# ESC_V1.net
KiCad netlist of a schematic drawn in Altium Designer
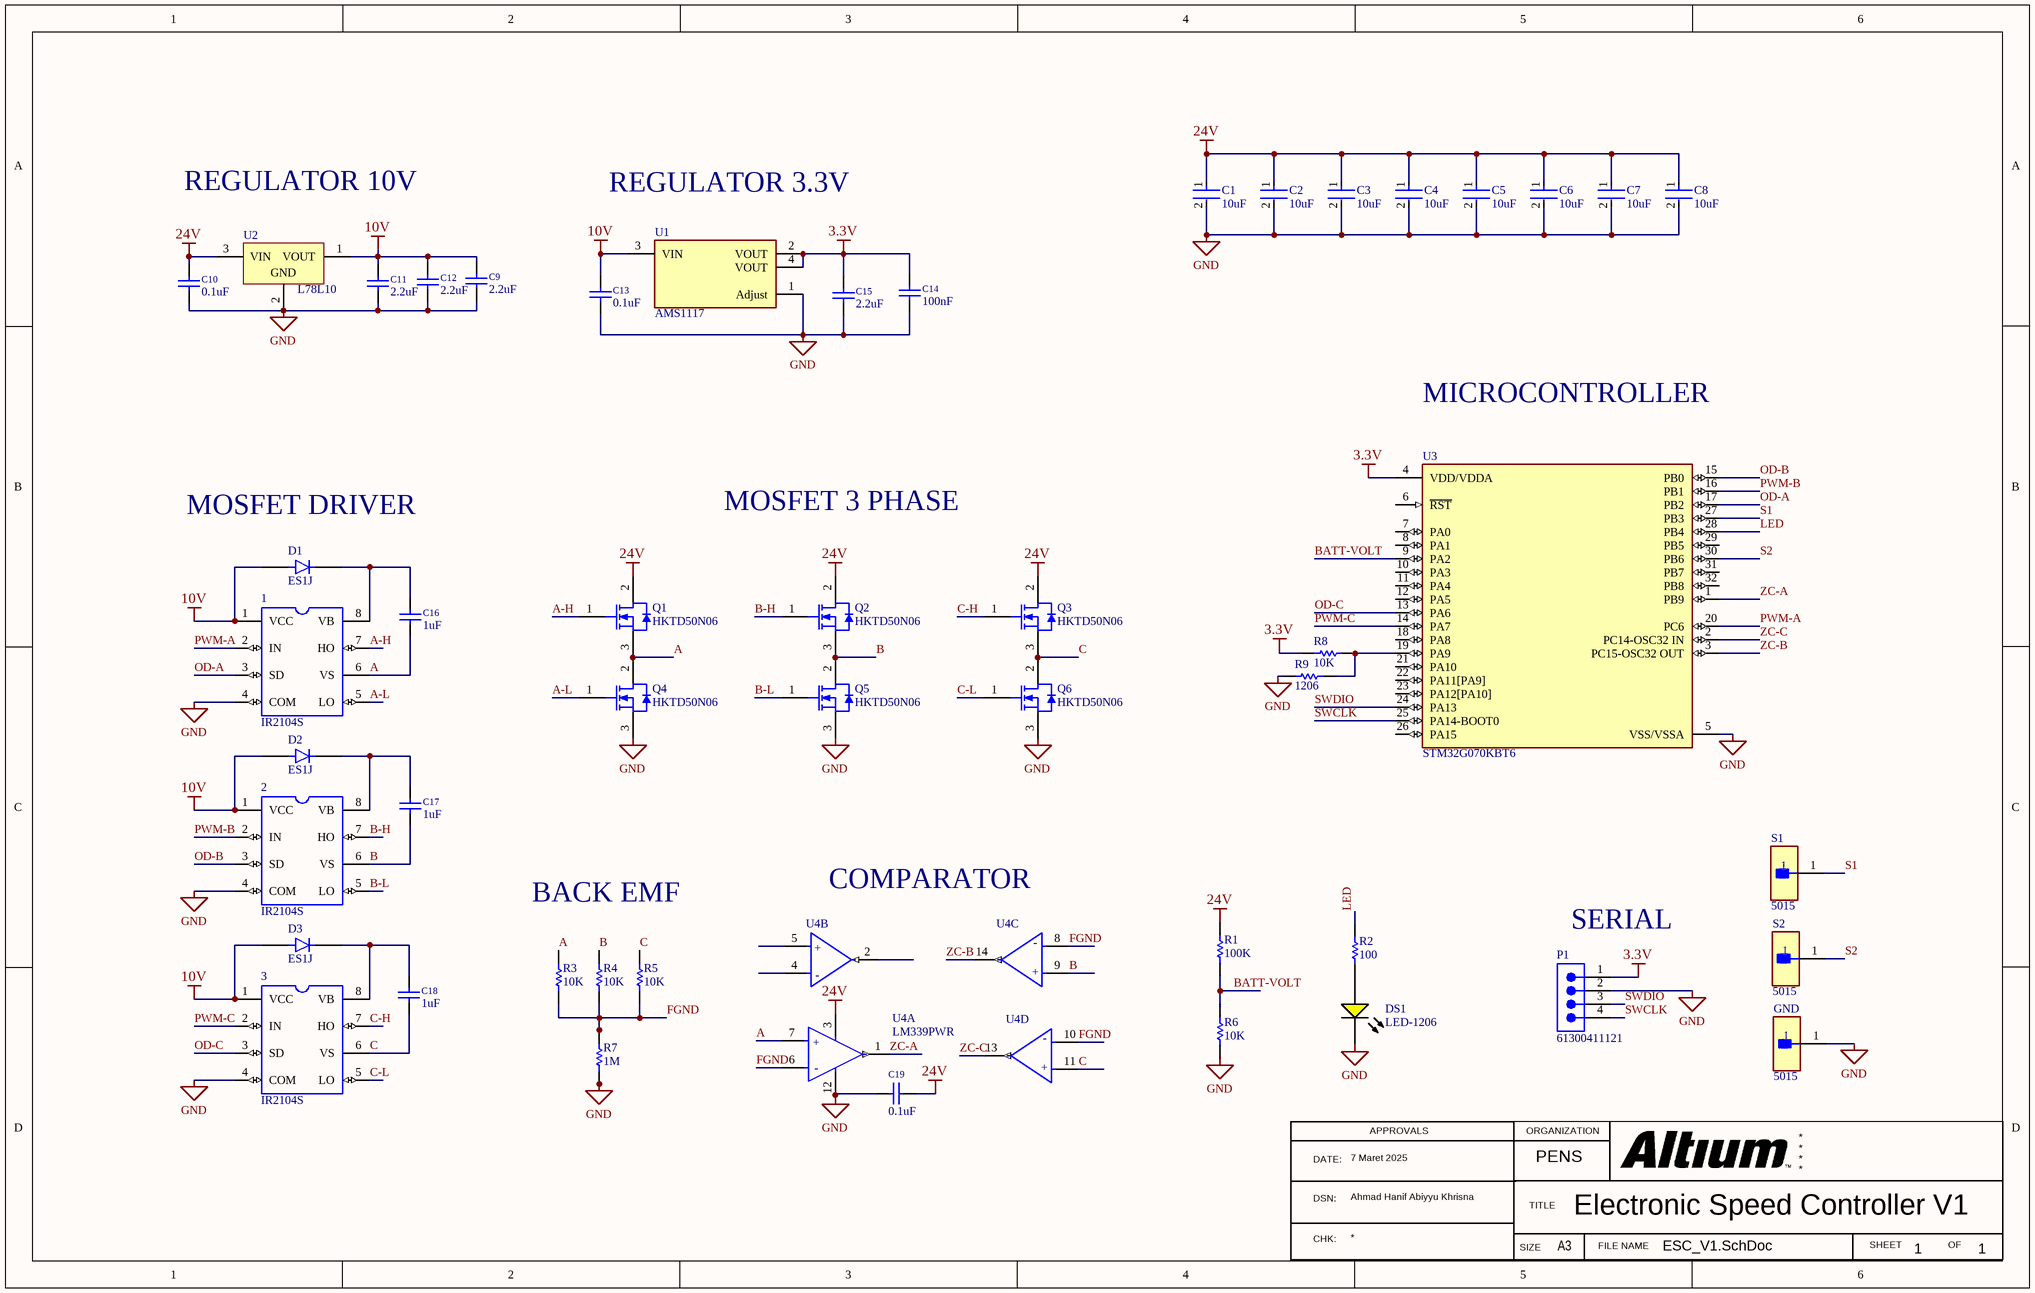
[diagram p0: ESC_V1.SchDoc]

(export (version "E")
  (design (tool "Eeschema 10.0.6"))
  (components
    (comp (ref "1")
      (value "IR2104S")
      (footprint "IR2104S")
      (description "Half-Bridge Gate Driver IC Non-Inverting 8-SOIC")
      (fields (field (name "MF") "Infineon Technologies"))
      (libsource (lib "IR2104S") (part "IR2104S"))
    )
    (comp (ref "2")
      (value "IR2104S")
      (footprint "IR2104S")
      (description "Half-Bridge Gate Driver IC Non-Inverting 8-SOIC")
      (fields (field (name "MF") "Infineon Technologies"))
      (libsource (lib "IR2104S") (part "IR2104S"))
    )
    (comp (ref "3")
      (value "IR2104S")
      (footprint "IR2104S")
      (description "Half-Bridge Gate Driver IC Non-Inverting 8-SOIC")
      (fields (field (name "MF") "Infineon Technologies"))
      (libsource (lib "IR2104S") (part "IR2104S"))
    )
    (comp (ref "C1")
      (value "10uF")
      (footprint "FP-C1206C-EB-IPC_A")
      (description "CAP CER 0.1UF 100V X7R 1206")
      (fields
        (field (name "TOLERANCE") "0.1")
        (field (name "OCTOPART") "https://octopart.com/c1206c104k1ractu-kemet-89521")
      )
      (libsource (lib "Altium Content Vault") (part "b4654b650e69147ec39a6b967a45e02"))
    )
    (comp (ref "C2")
      (value "10uF")
      (footprint "FP-C1206C-EB-IPC_A")
      (description "CAP CER 0.1UF 100V X7R 1206")
      (fields
        (field (name "TOLERANCE") "0.1")
        (field (name "OCTOPART") "https://octopart.com/c1206c104k1ractu-kemet-89521")
      )
      (libsource (lib "Altium Content Vault") (part "b4654b650e69147ec39a6b967a45e02"))
    )
    (comp (ref "C3")
      (value "10uF")
      (footprint "FP-C1206C-EB-IPC_A")
      (description "CAP CER 0.1UF 100V X7R 1206")
      (fields
        (field (name "TOLERANCE") "0.1")
        (field (name "OCTOPART") "https://octopart.com/c1206c104k1ractu-kemet-89521")
      )
      (libsource (lib "Altium Content Vault") (part "b4654b650e69147ec39a6b967a45e02"))
    )
    (comp (ref "C4")
      (value "10uF")
      (footprint "FP-C1206C-EB-IPC_A")
      (description "CAP CER 0.1UF 100V X7R 1206")
      (fields
        (field (name "TOLERANCE") "0.1")
        (field (name "OCTOPART") "https://octopart.com/c1206c104k1ractu-kemet-89521")
      )
      (libsource (lib "Altium Content Vault") (part "b4654b650e69147ec39a6b967a45e02"))
    )
    (comp (ref "C5")
      (value "10uF")
      (footprint "FP-C1206C-EB-IPC_A")
      (description "CAP CER 0.1UF 100V X7R 1206")
      (fields
        (field (name "TOLERANCE") "0.1")
        (field (name "OCTOPART") "https://octopart.com/c1206c104k1ractu-kemet-89521")
      )
      (libsource (lib "Altium Content Vault") (part "b4654b650e69147ec39a6b967a45e02"))
    )
    (comp (ref "C6")
      (value "10uF")
      (footprint "FP-C1206C-EB-IPC_A")
      (description "CAP CER 0.1UF 100V X7R 1206")
      (fields
        (field (name "TOLERANCE") "0.1")
        (field (name "OCTOPART") "https://octopart.com/c1206c104k1ractu-kemet-89521")
      )
      (libsource (lib "Altium Content Vault") (part "b4654b650e69147ec39a6b967a45e02"))
    )
    (comp (ref "C7")
      (value "10uF")
      (footprint "FP-C1206C-EB-IPC_A")
      (description "CAP CER 0.1UF 100V X7R 1206")
      (fields
        (field (name "TOLERANCE") "0.1")
        (field (name "OCTOPART") "https://octopart.com/c1206c104k1ractu-kemet-89521")
      )
      (libsource (lib "Altium Content Vault") (part "b4654b650e69147ec39a6b967a45e02"))
    )
    (comp (ref "C8")
      (value "10uF")
      (footprint "FP-C1206C-EB-IPC_A")
      (description "CAP CER 0.1UF 100V X7R 1206")
      (fields
        (field (name "TOLERANCE") "0.1")
        (field (name "OCTOPART") "https://octopart.com/c1206c104k1ractu-kemet-89521")
      )
      (libsource (lib "Altium Content Vault") (part "b4654b650e69147ec39a6b967a45e02"))
    )
    (comp (ref "C9")
      (value "2.2uF")
      (footprint "C2012-0805")
      (description "Capacitor")
      (fields (field (name "PUBLISHER") "Hoang Nguyen"))
      (libsource (lib "Lib1") (part "Capacitor"))
    )
    (comp (ref "C10")
      (value "0.1uF")
      (footprint "C2012-0805")
      (description "Capacitor")
      (fields (field (name "PUBLISHER") "Hoang Nguyen"))
      (libsource (lib "Lib1") (part "Capacitor"))
    )
    (comp (ref "C11")
      (value "2.2uF")
      (footprint "C2012-0805")
      (description "Capacitor")
      (fields (field (name "PUBLISHER") "Hoang Nguyen"))
      (libsource (lib "Lib1") (part "Capacitor"))
    )
    (comp (ref "C12")
      (value "2.2uF")
      (footprint "C2012-0805")
      (description "Capacitor")
      (fields (field (name "PUBLISHER") "Hoang Nguyen"))
      (libsource (lib "Lib1") (part "Capacitor"))
    )
    (comp (ref "C13")
      (value "0.1uF")
      (footprint "C2012-0805")
      (description "Capacitor")
      (fields (field (name "PUBLISHER") "Hoang Nguyen"))
      (libsource (lib "Lib1") (part "Capacitor"))
    )
    (comp (ref "C14")
      (value "100nF")
      (footprint "C2012-0805")
      (description "Capacitor")
      (fields (field (name "PUBLISHER") "Hoang Nguyen"))
      (libsource (lib "Lib1") (part "Capacitor"))
    )
    (comp (ref "C15")
      (value "2.2uF")
      (footprint "C2012-0805")
      (description "Capacitor")
      (fields (field (name "PUBLISHER") "Hoang Nguyen"))
      (libsource (lib "Lib1") (part "Capacitor"))
    )
    (comp (ref "C16")
      (value "1uF")
      (footprint "C2012-0805")
      (description "Capacitor")
      (fields (field (name "PUBLISHER") "Hoang Nguyen"))
      (libsource (lib "Lib1") (part "Capacitor"))
    )
    (comp (ref "C17")
      (value "1uF")
      (footprint "C2012-0805")
      (description "Capacitor")
      (fields (field (name "PUBLISHER") "Hoang Nguyen"))
      (libsource (lib "Lib1") (part "Capacitor"))
    )
    (comp (ref "C18")
      (value "1uF")
      (footprint "C2012-0805")
      (description "Capacitor")
      (fields (field (name "PUBLISHER") "Hoang Nguyen"))
      (libsource (lib "Lib1") (part "Capacitor"))
    )
    (comp (ref "C19")
      (value "0.1uF")
      (footprint "C2012-0805")
      (description "Capacitor")
      (fields (field (name "PUBLISHER") "Hoang Nguyen"))
      (libsource (lib "Lib1") (part "Capacitor"))
    )
    (comp (ref "D1")
      (value "ES1J")
      (footprint "DIO_ES1J")
      (description "Diode Standard 600V 1A Surface Mount SMA (DO-214AC)")
      (fields (field (name "MF") "ON Semiconductor"))
      (libsource (lib "ES1J") (part "ES1J"))
    )
    (comp (ref "D2")
      (value "ES1J")
      (footprint "DIO_ES1J")
      (description "Diode Standard 600V 1A Surface Mount SMA (DO-214AC)")
      (fields (field (name "MF") "ON Semiconductor"))
      (libsource (lib "ES1J") (part "ES1J"))
    )
    (comp (ref "D3")
      (value "ES1J")
      (footprint "DIO_ES1J")
      (description "Diode Standard 600V 1A Surface Mount SMA (DO-214AC)")
      (fields (field (name "MF") "ON Semiconductor"))
      (libsource (lib "ES1J") (part "ES1J"))
    )
    (comp (ref "DS1")
      (value "LED-1206")
      (footprint "LUMX-SML-LX1206YC-TR_V")
      (description "Yellow LED, Water Clear Len, 585 nm, 2.1 V, -40 to 85 degC, 2-Pin SMD, RoHS, Tape and Reel")
      (fields (field (name "MANUFACTURER") "Lumex"))
      (libsource (lib "Altium Content Vault") (part "LED-YELLOW-AK-2"))
    )
    (comp (ref "GND")
      (value "5015")
      (footprint "FP-5015-MFG")
      (description "PC TEST POINT MINIATURE")
      (fields
        (field (name "MANUFACTURER") "keystone")
        (field (name "OCTOPART") "https://octopart.com/5015-keystone-3822")
      )
      (libsource (lib "Altium Content Vault") (part "dd45045ce8184df9e99e12baf3f412c"))
    )
    (comp (ref "P1")
      (value "61300411121")
      (footprint "61300411121")
      (libsource (lib "Altium Content Vault") (part "Header_Male_1R_04P"))
    )
    (comp (ref "Q1")
      (value "HKTD50N06")
      (footprint "INF-PG-TO252-3-313_L")
      (fields (field (name "MANUFACTURER") "Infineon") (field (name "PARTNUMBER") "IPD60R600C6"))
      (libsource (lib "Altium Content Vault") (part "INF-NEMOS-GDS-3"))
    )
    (comp (ref "Q2")
      (value "HKTD50N06")
      (footprint "INF-PG-TO252-3-313_L")
      (fields (field (name "MANUFACTURER") "Infineon") (field (name "PARTNUMBER") "IPD60R600C6"))
      (libsource (lib "Altium Content Vault") (part "INF-NEMOS-GDS-3"))
    )
    (comp (ref "Q3")
      (value "HKTD50N06")
      (footprint "INF-PG-TO252-3-313_L")
      (fields (field (name "MANUFACTURER") "Infineon") (field (name "PARTNUMBER") "IPD60R600C6"))
      (libsource (lib "Altium Content Vault") (part "INF-NEMOS-GDS-3"))
    )
    (comp (ref "Q4")
      (value "HKTD50N06")
      (footprint "INF-PG-TO252-3-313_L")
      (fields (field (name "MANUFACTURER") "Infineon") (field (name "PARTNUMBER") "IPD60R600C6"))
      (libsource (lib "Altium Content Vault") (part "INF-NEMOS-GDS-3"))
    )
    (comp (ref "Q5")
      (value "HKTD50N06")
      (footprint "INF-PG-TO252-3-313_L")
      (fields (field (name "MANUFACTURER") "Infineon") (field (name "PARTNUMBER") "IPD60R600C6"))
      (libsource (lib "Altium Content Vault") (part "INF-NEMOS-GDS-3"))
    )
    (comp (ref "Q6")
      (value "HKTD50N06")
      (footprint "INF-PG-TO252-3-313_L")
      (fields (field (name "MANUFACTURER") "Infineon") (field (name "PARTNUMBER") "IPD60R600C6"))
      (libsource (lib "Altium Content Vault") (part "INF-NEMOS-GDS-3"))
    )
    (comp (ref "R1")
      (value "100K")
      (footprint "RESC2013X50X30NL20T20")
      (fields (field (name "MANUFACTURER") "Vishay Dale") (field (name "PART NUMBER") "CRCW080510R0FKEA"))
      (libsource (lib "Altium Content Vault") (part "RES"))
    )
    (comp (ref "R2")
      (value "100")
      (footprint "RESC3216X70X50NL05T20")
      (fields (field (name "MANUFACTURER") "Panasonic") (field (name "PART NUMBER") "ERJ-8GEY0R00V"))
      (libsource (lib "Altium Content Vault") (part "RES"))
    )
    (comp (ref "R3")
      (value "10K")
      (footprint "RESC2013X50X30NL20T20")
      (fields (field (name "MANUFACTURER") "Vishay Dale") (field (name "PART NUMBER") "CRCW080510R0FKEA"))
      (libsource (lib "Altium Content Vault") (part "RES"))
    )
    (comp (ref "R4")
      (value "10K")
      (footprint "RESC2013X50X30NL20T20")
      (fields (field (name "MANUFACTURER") "Vishay Dale") (field (name "PART NUMBER") "CRCW080510R0FKEA"))
      (libsource (lib "Altium Content Vault") (part "RES"))
    )
    (comp (ref "R5")
      (value "10K")
      (footprint "RESC2013X50X30NL20T20")
      (fields (field (name "MANUFACTURER") "Vishay Dale") (field (name "PART NUMBER") "CRCW080510R0FKEA"))
      (libsource (lib "Altium Content Vault") (part "RES"))
    )
    (comp (ref "R6")
      (value "10K")
      (footprint "RESC2013X50X30NL20T20")
      (fields (field (name "MANUFACTURER") "Vishay Dale") (field (name "PART NUMBER") "CRCW080510R0FKEA"))
      (libsource (lib "Altium Content Vault") (part "RES"))
    )
    (comp (ref "R7")
      (value "1M")
      (footprint "RESC2013X50X30NL20T20")
      (fields (field (name "MANUFACTURER") "Vishay Dale") (field (name "PART NUMBER") "CRCW080510R0FKEA"))
      (libsource (lib "Altium Content Vault") (part "RES"))
    )
    (comp (ref "R8")
      (value "10K")
      (footprint "RESC2013X50X30NL20T20")
      (fields (field (name "MANUFACTURER") "Vishay Dale") (field (name "PART NUMBER") "CRCW080510R0FKEA"))
      (libsource (lib "Altium Content Vault") (part "RES"))
    )
    (comp (ref "R9")
      (value "1206")
      (footprint "RESC3216X70X50NL05T20")
      (fields (field (name "MANUFACTURER") "Panasonic") (field (name "PART NUMBER") "ERJ-8GEY0R00V"))
      (libsource (lib "Altium Content Vault") (part "RES"))
    )
    (comp (ref "S1")
      (value "5015")
      (footprint "FP-5015-MFG")
      (description "PC TEST POINT MINIATURE")
      (fields
        (field (name "MANUFACTURER") "keystone")
        (field (name "OCTOPART") "https://octopart.com/5015-keystone-3822")
      )
      (libsource (lib "Altium Content Vault") (part "dd45045ce8184df9e99e12baf3f412c"))
    )
    (comp (ref "S2")
      (value "5015")
      (footprint "FP-5015-MFG")
      (description "PC TEST POINT MINIATURE")
      (fields
        (field (name "MANUFACTURER") "keystone")
        (field (name "OCTOPART") "https://octopart.com/5015-keystone-3822")
      )
      (libsource (lib "Altium Content Vault") (part "dd45045ce8184df9e99e12baf3f412c"))
    )
    (comp (ref "U1")
      (value "AMS1117")
      (footprint "FP-ams1117-IPC_B")
      (description "1A LOW DROPOUT VOLTAGE REGULATOR")
      (libsource (lib "Altium Content Vault") (part "59ad430b93a2c51b3e6ee7c3b069677"))
    )
    (comp (ref "U2")
      (value "L78L10")
      (footprint "SOT-89_M")
      (description "Positive Voltage Regulator, 10V, 4-Pin SOT-89, Tape and Reel")
      (libsource (lib "Altium Content Vault") (part "PM-REG-7805-SIL3"))
    )
    (comp (ref "U3")
      (value "STM32G070KBT6")
      (footprint "FP-LQFP32-5V-MFG")
      (description "MAINSTREAM VALUE LINE, ARM CORTE")
      (fields
        (field (name "OCTOPART") "https://octopart.com/stm32g070kbt6-stmicroelectronics-97300430")
        (field (name "MANUFACTURER") "STMicroelectronics")
      )
      (libsource (lib "Altium Content Vault") (part "198924d13b8f9d845b03e0f7fb09701"))
    )
    (comp (ref "U4")
      (value "LM339PWR")
      (footprint "FP-PW0014A-IPC_A")
      (description "IC QUAD DIFF COMPARATOR 14-TSSOP")
      (libsource (lib "Altium Content Vault") (part "194f83ff06066585c623a61d885a339"))
    )
  )
  (nets
    (net (code "1") (name "/A") (class "Default")
      (node (ref "1") (pin "6") (pinfunction "VS_6") (pintype "power_in"))
      (node (ref "C16") (pin "2") (pinfunction "2_2") (pintype "passive"))
      (node (ref "Q1") (pin "3") (pinfunction "SOURCE_3") (pintype "passive"))
      (node (ref "Q4") (pin "2") (pinfunction "DRAIN_2") (pintype "passive"))
      (node (ref "R3") (pin "2") (pinfunction "2_2") (pintype "passive"))
      (node (ref "U4") (pin "7") (pinfunction "1IN+_7") (pintype "tri_state"))
    )
    (net (code "2") (name "/A-H") (class "Default")
      (node (ref "1") (pin "7") (pinfunction "HO_7") (pintype "bidirectional"))
      (node (ref "Q1") (pin "1") (pinfunction "GATE_1") (pintype "passive"))
    )
    (net (code "3") (name "/A-L") (class "Default")
      (node (ref "1") (pin "5") (pinfunction "LO_5") (pintype "bidirectional"))
      (node (ref "Q4") (pin "1") (pinfunction "GATE_1") (pintype "passive"))
    )
    (net (code "4") (name "/B") (class "Default")
      (node (ref "2") (pin "6") (pinfunction "VS_6") (pintype "power_in"))
      (node (ref "C17") (pin "2") (pinfunction "2_2") (pintype "passive"))
      (node (ref "Q2") (pin "3") (pinfunction "SOURCE_3") (pintype "passive"))
      (node (ref "Q5") (pin "2") (pinfunction "DRAIN_2") (pintype "passive"))
      (node (ref "R4") (pin "2") (pinfunction "2_2") (pintype "passive"))
      (node (ref "U4") (pin "9") (pinfunction "3IN+_9") (pintype "tri_state"))
    )
    (net (code "5") (name "/B-H") (class "Default")
      (node (ref "2") (pin "7") (pinfunction "HO_7") (pintype "bidirectional"))
      (node (ref "Q2") (pin "1") (pinfunction "GATE_1") (pintype "passive"))
    )
    (net (code "6") (name "/B-L") (class "Default")
      (node (ref "2") (pin "5") (pinfunction "LO_5") (pintype "bidirectional"))
      (node (ref "Q5") (pin "1") (pinfunction "GATE_1") (pintype "passive"))
    )
    (net (code "7") (name "/BATT-VOLT") (class "Default")
      (node (ref "R1") (pin "1") (pinfunction "1_1") (pintype "passive"))
      (node (ref "R6") (pin "2") (pinfunction "2_2") (pintype "passive"))
      (node (ref "U3") (pin "9") (pinfunction "PA2_9") (pintype "bidirectional"))
    )
    (net (code "8") (name "/C") (class "Default")
      (node (ref "3") (pin "6") (pinfunction "VS_6") (pintype "power_in"))
      (node (ref "C18") (pin "2") (pinfunction "2_2") (pintype "passive"))
      (node (ref "Q3") (pin "3") (pinfunction "SOURCE_3") (pintype "passive"))
      (node (ref "Q6") (pin "2") (pinfunction "DRAIN_2") (pintype "passive"))
      (node (ref "R5") (pin "2") (pinfunction "2_2") (pintype "passive"))
      (node (ref "U4") (pin "11") (pinfunction "4IN+_11") (pintype "tri_state"))
    )
    (net (code "9") (name "/C-H") (class "Default")
      (node (ref "3") (pin "7") (pinfunction "HO_7") (pintype "bidirectional"))
      (node (ref "Q3") (pin "1") (pinfunction "GATE_1") (pintype "passive"))
    )
    (net (code "10") (name "/C-L") (class "Default")
      (node (ref "3") (pin "5") (pinfunction "LO_5") (pintype "bidirectional"))
      (node (ref "Q6") (pin "1") (pinfunction "GATE_1") (pintype "passive"))
    )
    (net (code "11") (name "/FGND") (class "Default")
      (node (ref "R3") (pin "1") (pinfunction "1_1") (pintype "passive"))
      (node (ref "R4") (pin "1") (pinfunction "1_1") (pintype "passive"))
      (node (ref "R5") (pin "1") (pinfunction "1_1") (pintype "passive"))
      (node (ref "R7") (pin "2") (pinfunction "2_2") (pintype "passive"))
      (node (ref "U4") (pin "10") (pinfunction "4IN-_10") (pintype "tri_state"))
      (node (ref "U4") (pin "6") (pinfunction "1IN-_6") (pintype "tri_state"))
      (node (ref "U4") (pin "8") (pinfunction "3IN-_8") (pintype "tri_state"))
    )
    (net (code "12") (name "/LED") (class "Default")
      (node (ref "R2") (pin "2") (pinfunction "2_2") (pintype "passive"))
      (node (ref "U3") (pin "28") (pinfunction "PB4_28") (pintype "bidirectional"))
    )
    (net (code "13") (name "/OD-A") (class "Default")
      (node (ref "1") (pin "3") (pinfunction "SD_3") (pintype "bidirectional"))
      (node (ref "U3") (pin "17") (pinfunction "PB2_17") (pintype "bidirectional"))
    )
    (net (code "14") (name "/OD-B") (class "Default")
      (node (ref "2") (pin "3") (pinfunction "SD_3") (pintype "bidirectional"))
      (node (ref "U3") (pin "15") (pinfunction "PB0_15") (pintype "bidirectional"))
    )
    (net (code "15") (name "/OD-C") (class "Default")
      (node (ref "3") (pin "3") (pinfunction "SD_3") (pintype "bidirectional"))
      (node (ref "U3") (pin "13") (pinfunction "PA6_13") (pintype "bidirectional"))
    )
    (net (code "16") (name "/PWM-A") (class "Default")
      (node (ref "1") (pin "2") (pinfunction "IN_2") (pintype "bidirectional"))
      (node (ref "U3") (pin "20") (pinfunction "PC6_20") (pintype "bidirectional"))
    )
    (net (code "17") (name "/PWM-B") (class "Default")
      (node (ref "2") (pin "2") (pinfunction "IN_2") (pintype "bidirectional"))
      (node (ref "U3") (pin "16") (pinfunction "PB1_16") (pintype "bidirectional"))
    )
    (net (code "18") (name "/PWM-C") (class "Default")
      (node (ref "3") (pin "2") (pinfunction "IN_2") (pintype "bidirectional"))
      (node (ref "U3") (pin "14") (pinfunction "PA7_14") (pintype "bidirectional"))
    )
    (net (code "19") (name "/S1") (class "Default")
      (node (ref "S1") (pin "1") (pinfunction "1_1") (pintype "passive"))
      (node (ref "U3") (pin "27") (pinfunction "PB3_27") (pintype "bidirectional"))
    )
    (net (code "20") (name "/S2") (class "Default")
      (node (ref "S2") (pin "1") (pinfunction "1_1") (pintype "passive"))
      (node (ref "U3") (pin "30") (pinfunction "PB6_30") (pintype "bidirectional"))
    )
    (net (code "21") (name "/SWCLK") (class "Default")
      (node (ref "P1") (pin "4") (pinfunction "4_4") (pintype "passive"))
      (node (ref "U3") (pin "25") (pinfunction "PA14-BOOT0_25") (pintype "bidirectional"))
    )
    (net (code "22") (name "/SWDIO") (class "Default")
      (node (ref "P1") (pin "3") (pinfunction "3_3") (pintype "passive"))
      (node (ref "U3") (pin "24") (pinfunction "PA13_24") (pintype "bidirectional"))
    )
    (net (code "23") (name "/ZC-A") (class "Default")
      (node (ref "U3") (pin "1") (pinfunction "PB9_1") (pintype "bidirectional"))
      (node (ref "U4") (pin "1") (pinfunction "1OUT_1") (pintype "output"))
    )
    (net (code "24") (name "/ZC-B") (class "Default")
      (node (ref "U3") (pin "3") (pinfunction "PC15-OSC32_OUT_3") (pintype "bidirectional"))
      (node (ref "U4") (pin "14") (pinfunction "OUT3_14") (pintype "output"))
    )
    (net (code "25") (name "/ZC-C") (class "Default")
      (node (ref "U3") (pin "2") (pinfunction "PC14-OSC32_IN_2") (pintype "bidirectional"))
      (node (ref "U4") (pin "13") (pinfunction "OUT4_13") (pintype "output"))
    )
    (net (code "26") (name "3.3V") (class "Default")
      (node (ref "C14") (pin "1") (pinfunction "1_1") (pintype "passive"))
      (node (ref "C15") (pin "1") (pinfunction "1_1") (pintype "passive"))
      (node (ref "P1") (pin "1") (pinfunction "1_1") (pintype "passive"))
      (node (ref "R8") (pin "2") (pinfunction "2_2") (pintype "passive"))
      (node (ref "U1") (pin "2") (pinfunction "VOUT_2") (pintype "passive"))
      (node (ref "U1") (pin "4") (pinfunction "VOUT_4") (pintype "passive"))
      (node (ref "U3") (pin "4") (pinfunction "VDD/VDDA_4") (pintype "power_in"))
    )
    (net (code "27") (name "10V") (class "Default")
      (node (ref "1") (pin "1") (pinfunction "VCC_1") (pintype "power_in"))
      (node (ref "2") (pin "1") (pinfunction "VCC_1") (pintype "power_in"))
      (node (ref "3") (pin "1") (pinfunction "VCC_1") (pintype "power_in"))
      (node (ref "C11") (pin "1") (pinfunction "1_1") (pintype "passive"))
      (node (ref "C12") (pin "1") (pinfunction "1_1") (pintype "passive"))
      (node (ref "C13") (pin "1") (pinfunction "1_1") (pintype "passive"))
      (node (ref "C9") (pin "1") (pinfunction "1_1") (pintype "passive"))
      (node (ref "D1") (pin "A") (pinfunction "A_A") (pintype "passive"))
      (node (ref "D2") (pin "A") (pinfunction "A_A") (pintype "passive"))
      (node (ref "D3") (pin "A") (pinfunction "A_A") (pintype "passive"))
      (node (ref "U1") (pin "3") (pinfunction "VIN_3") (pintype "power_in"))
      (node (ref "U2") (pin "1") (pinfunction "VOUT_1") (pintype "power_in"))
    )
    (net (code "28") (name "24V") (class "Default")
      (node (ref "C1") (pin "1") (pinfunction "1_1") (pintype "passive"))
      (node (ref "C10") (pin "1") (pinfunction "1_1") (pintype "passive"))
      (node (ref "C19") (pin "1") (pinfunction "1_1") (pintype "passive"))
      (node (ref "C2") (pin "1") (pinfunction "1_1") (pintype "passive"))
      (node (ref "C3") (pin "1") (pinfunction "1_1") (pintype "passive"))
      (node (ref "C4") (pin "1") (pinfunction "1_1") (pintype "passive"))
      (node (ref "C5") (pin "1") (pinfunction "1_1") (pintype "passive"))
      (node (ref "C6") (pin "1") (pinfunction "1_1") (pintype "passive"))
      (node (ref "C7") (pin "1") (pinfunction "1_1") (pintype "passive"))
      (node (ref "C8") (pin "1") (pinfunction "1_1") (pintype "passive"))
      (node (ref "Q1") (pin "2") (pinfunction "DRAIN_2") (pintype "passive"))
      (node (ref "Q2") (pin "2") (pinfunction "DRAIN_2") (pintype "passive"))
      (node (ref "Q3") (pin "2") (pinfunction "DRAIN_2") (pintype "passive"))
      (node (ref "R1") (pin "2") (pinfunction "2_2") (pintype "passive"))
      (node (ref "U2") (pin "3") (pinfunction "VIN_3") (pintype "power_in"))
      (node (ref "U4") (pin "3") (pinfunction "VCC_3") (pintype "power_in"))
    )
    (net (code "29") (name "GND") (class "Default")
      (node (ref "1") (pin "4") (pinfunction "COM_4") (pintype "bidirectional"))
      (node (ref "2") (pin "4") (pinfunction "COM_4") (pintype "bidirectional"))
      (node (ref "3") (pin "4") (pinfunction "COM_4") (pintype "bidirectional"))
      (node (ref "C1") (pin "2") (pinfunction "2_2") (pintype "passive"))
      (node (ref "C10") (pin "2") (pinfunction "2_2") (pintype "passive"))
      (node (ref "C11") (pin "2") (pinfunction "2_2") (pintype "passive"))
      (node (ref "C12") (pin "2") (pinfunction "2_2") (pintype "passive"))
      (node (ref "C13") (pin "2") (pinfunction "2_2") (pintype "passive"))
      (node (ref "C14") (pin "2") (pinfunction "2_2") (pintype "passive"))
      (node (ref "C15") (pin "2") (pinfunction "2_2") (pintype "passive"))
      (node (ref "C19") (pin "2") (pinfunction "2_2") (pintype "passive"))
      (node (ref "C2") (pin "2") (pinfunction "2_2") (pintype "passive"))
      (node (ref "C3") (pin "2") (pinfunction "2_2") (pintype "passive"))
      (node (ref "C4") (pin "2") (pinfunction "2_2") (pintype "passive"))
      (node (ref "C5") (pin "2") (pinfunction "2_2") (pintype "passive"))
      (node (ref "C6") (pin "2") (pinfunction "2_2") (pintype "passive"))
      (node (ref "C7") (pin "2") (pinfunction "2_2") (pintype "passive"))
      (node (ref "C8") (pin "2") (pinfunction "2_2") (pintype "passive"))
      (node (ref "C9") (pin "2") (pinfunction "2_2") (pintype "passive"))
      (node (ref "DS1") (pin "2") (pinfunction "K_2") (pintype "passive"))
      (node (ref "GND") (pin "1") (pinfunction "1_1") (pintype "passive"))
      (node (ref "P1") (pin "2") (pinfunction "2_2") (pintype "passive"))
      (node (ref "Q4") (pin "3") (pinfunction "SOURCE_3") (pintype "passive"))
      (node (ref "Q5") (pin "3") (pinfunction "SOURCE_3") (pintype "passive"))
      (node (ref "Q6") (pin "3") (pinfunction "SOURCE_3") (pintype "passive"))
      (node (ref "R6") (pin "1") (pinfunction "1_1") (pintype "passive"))
      (node (ref "R7") (pin "1") (pinfunction "1_1") (pintype "passive"))
      (node (ref "R9") (pin "1") (pinfunction "1_1") (pintype "passive"))
      (node (ref "U1") (pin "1") (pinfunction "Adjust_1") (pintype "passive"))
      (node (ref "U2") (pin "2") (pinfunction "GND_2") (pintype "power_in"))
      (node (ref "U3") (pin "5") (pinfunction "VSS/VSSA_5") (pintype "power_in"))
      (node (ref "U4") (pin "12") (pinfunction "GND_12") (pintype "power_in"))
    )
    (net (code "30") (name "Net-(1-VB)") (class "Default")
      (node (ref "1") (pin "8") (pinfunction "VB_8") (pintype "power_in"))
      (node (ref "C16") (pin "1") (pinfunction "1_1") (pintype "passive"))
      (node (ref "D1") (pin "K") (pinfunction "K_K") (pintype "passive"))
    )
    (net (code "31") (name "Net-(2-VB)") (class "Default")
      (node (ref "2") (pin "8") (pinfunction "VB_8") (pintype "power_in"))
      (node (ref "C17") (pin "1") (pinfunction "1_1") (pintype "passive"))
      (node (ref "D2") (pin "K") (pinfunction "K_K") (pintype "passive"))
    )
    (net (code "32") (name "Net-(3-VB)") (class "Default")
      (node (ref "3") (pin "8") (pinfunction "VB_8") (pintype "power_in"))
      (node (ref "C18") (pin "1") (pinfunction "1_1") (pintype "passive"))
      (node (ref "D3") (pin "K") (pinfunction "K_K") (pintype "passive"))
    )
    (net (code "33") (name "Net-(DS1-A)") (class "Default")
      (node (ref "DS1") (pin "1") (pinfunction "A_1") (pintype "passive"))
      (node (ref "R2") (pin "1") (pinfunction "1_1") (pintype "passive"))
    )
    (net (code "34") (name "Net-(U3-PA9)") (class "Default")
      (node (ref "R8") (pin "1") (pinfunction "1_1") (pintype "passive"))
      (node (ref "R9") (pin "2") (pinfunction "2_2") (pintype "passive"))
      (node (ref "U3") (pin "19") (pinfunction "PA9_19") (pintype "bidirectional"))
    )
    (net (code "35") (name "unconnected-(U3-PA0-Pad7)") (class "Default")
      (node (ref "U3") (pin "7") (pinfunction "PA0_7") (pintype "bidirectional"))
    )
    (net (code "36") (name "unconnected-(U3-PA1-Pad8)") (class "Default")
      (node (ref "U3") (pin "8") (pinfunction "PA1_8") (pintype "bidirectional"))
    )
    (net (code "37") (name "unconnected-(U3-PA3-Pad10)") (class "Default")
      (node (ref "U3") (pin "10") (pinfunction "PA3_10") (pintype "bidirectional"))
    )
    (net (code "38") (name "unconnected-(U3-PA4-Pad11)") (class "Default")
      (node (ref "U3") (pin "11") (pinfunction "PA4_11") (pintype "bidirectional"))
    )
    (net (code "39") (name "unconnected-(U3-PA5-Pad12)") (class "Default")
      (node (ref "U3") (pin "12") (pinfunction "PA5_12") (pintype "bidirectional"))
    )
    (net (code "40") (name "unconnected-(U3-PA8-Pad18)") (class "Default")
      (node (ref "U3") (pin "18") (pinfunction "PA8_18") (pintype "bidirectional"))
    )
    (net (code "41") (name "unconnected-(U3-PA10-Pad21)") (class "Default")
      (node (ref "U3") (pin "21") (pinfunction "PA10_21") (pintype "bidirectional"))
    )
    (net (code "42") (name "unconnected-(U3-PA11[PA9]-Pad22)") (class "Default")
      (node (ref "U3") (pin "22") (pinfunction "PA11[PA9]_22") (pintype "bidirectional"))
    )
    (net (code "43") (name "unconnected-(U3-PA12[PA10]-Pad23)") (class "Default")
      (node (ref "U3") (pin "23") (pinfunction "PA12[PA10]_23") (pintype "bidirectional"))
    )
    (net (code "44") (name "unconnected-(U3-PA15-Pad26)") (class "Default")
      (node (ref "U3") (pin "26") (pinfunction "PA15_26") (pintype "bidirectional"))
    )
    (net (code "45") (name "unconnected-(U3-PB5-Pad29)") (class "Default")
      (node (ref "U3") (pin "29") (pinfunction "PB5_29") (pintype "bidirectional"))
    )
    (net (code "46") (name "unconnected-(U3-PB7-Pad31)") (class "Default")
      (node (ref "U3") (pin "31") (pinfunction "PB7_31") (pintype "bidirectional"))
    )
    (net (code "47") (name "unconnected-(U3-PB8-Pad32)") (class "Default")
      (node (ref "U3") (pin "32") (pinfunction "PB8_32") (pintype "bidirectional"))
    )
    (net (code "48") (name "unconnected-(U3-~{RST}-Pad6)") (class "Default")
      (node (ref "U3") (pin "6") (pinfunction "~{RST}_6") (pintype "input"))
    )
    (net (code "49") (name "unconnected-(U4B-2IN+-Pad5)") (class "Default")
      (node (ref "U4") (pin "5") (pinfunction "2IN+_5") (pintype "tri_state"))
    )
    (net (code "50") (name "unconnected-(U4B-2IN--Pad4)") (class "Default")
      (node (ref "U4") (pin "4") (pinfunction "2IN-_4") (pintype "tri_state"))
    )
    (net (code "51") (name "unconnected-(U4B-2OUT-Pad2)") (class "Default")
      (node (ref "U4") (pin "2") (pinfunction "2OUT_2") (pintype "input"))
    )
  )
)
